# 24_063_24_069.net
KiCad netlist of a schematic drawn in Altium Designer
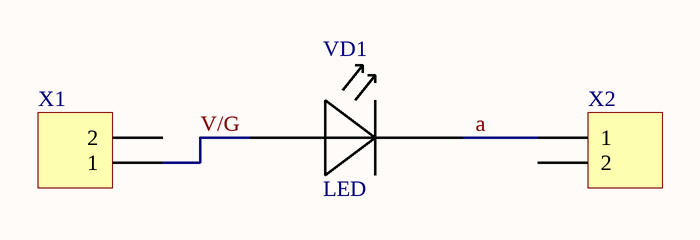
[diagram p0: 24.063_24.069.SchDoc]

(export (version "E")
  (design (tool "Eeschema 10.0.6"))
  (components
    (comp (ref "VD1") (value "LED") (footprint "LED 24.063") (libsource (lib "msp_SchLib") (part "LED")))
    (comp (ref "X1")
      (value "Header 2")
      (footprint "HDR1X2")
      (description "Header, 2-Pin")
      (fields (field (name "PUBLISHER") "Altium Limited"))
      (libsource (lib "Miscellaneous Connectors") (part "Header 2"))
    )
    (comp (ref "X2")
      (value "Header 2")
      (footprint "HDR1X2")
      (description "Header, 2-Pin")
      (fields (field (name "PUBLISHER") "Altium Limited"))
      (libsource (lib "") (part "Header 2_1"))
    )
  )
  (nets
    (net (code "1") (name "/V{slash}G") (class "Default")
      (node (ref "VD1") (pin "1") (pinfunction "1_1") (pintype "passive"))
      (node (ref "X1") (pin "1") (pinfunction "1_1") (pintype "passive"))
    )
    (net (code "2") (name "/a") (class "Default")
      (node (ref "VD1") (pin "2") (pinfunction "2_2") (pintype "passive"))
      (node (ref "X2") (pin "1") (pinfunction "1_1") (pintype "passive"))
    )
    (net (code "3") (name "unconnected-(X1-Pad2)") (class "Default")
      (node (ref "X1") (pin "2") (pinfunction "2_2") (pintype "passive"))
    )
    (net (code "4") (name "unconnected-(X2-Pad2)") (class "Default")
      (node (ref "X2") (pin "2") (pinfunction "2_2") (pintype "passive"))
    )
  )
)
